# Sheet1.net
KiCad netlist of a schematic drawn in Altium Designer
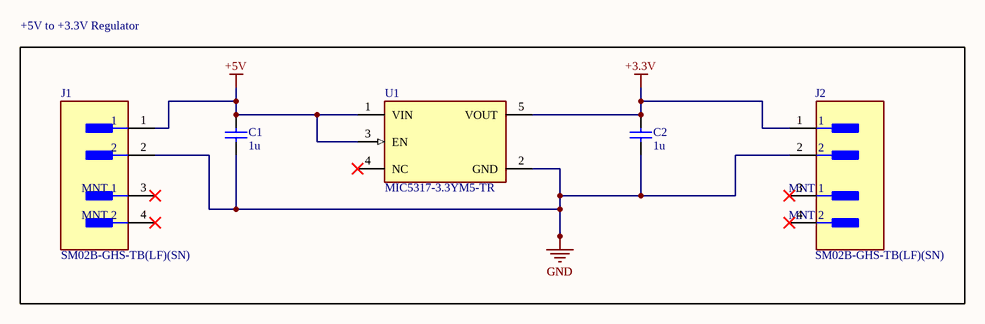
[diagram p0: Sheet1.SchDoc]

(export (version "E")
  (design (tool "Eeschema 10.0.6"))
  (components
    (comp (ref "C1")
      (value "1u")
      (footprint "CAPC2013X140X50ML20T25")
      (fields
        (field (name "MANUFACTURER") "AVX Interconnect / Elco")
        (field (name "PART NUMBER") "0805ZD105KAT2A")
      )
      (libsource (lib "Altium Content Vault") (part "CAP"))
    )
    (comp (ref "C2")
      (value "1u")
      (footprint "CAPC2013X140X50ML20T25")
      (fields
        (field (name "MANUFACTURER") "AVX Interconnect / Elco")
        (field (name "PART NUMBER") "0805ZD105KAT2A")
      )
      (libsource (lib "Altium Content Vault") (part "CAP"))
    )
    (comp (ref "J1")
      (value "SM02B-GHS-TB(LF)(SN)")
      (footprint "FP-SM02B-GHS-TB_LF_SN-MFG")
      (description "CONN HEADER SMD R/A 2POS 1.25MM")
      (libsource (lib "") (part "56ec3178a87b3978bdc1b3682cd516a_1"))
    )
    (comp (ref "J2")
      (value "SM02B-GHS-TB(LF)(SN)")
      (footprint "FP-SM02B-GHS-TB_LF_SN-MFG")
      (description "CONN HEADER SMD R/A 2POS 1.25MM")
      (libsource (lib "Altium Content Vault") (part "56ec3178a87b3978bdc1b3682cd516a"))
    )
    (comp (ref "U1")
      (value "MIC5317-3.3YM5-TR")
      (footprint "FP-SOT23-5LD-PL-1-MFG")
      (description "IC REG LINEAR 3.3V 150MA SOT23-5")
      (libsource (lib "Altium Content Vault") (part "0a093dae7315cdc977fd108dde87457"))
    )
  )
  (nets
    (net (code "1") (name "+3.3V") (class "Default")
      (node (ref "C2") (pin "2") (pinfunction "2_2") (pintype "passive"))
      (node (ref "J2") (pin "1") (pinfunction "1_1") (pintype "passive"))
      (node (ref "U1") (pin "5") (pinfunction "VOUT_5") (pintype "power_in"))
    )
    (net (code "2") (name "+5V") (class "Default")
      (node (ref "C1") (pin "1") (pinfunction "1_1") (pintype "passive"))
      (node (ref "J1") (pin "1") (pinfunction "1_1") (pintype "passive"))
      (node (ref "U1") (pin "1") (pinfunction "VIN_1") (pintype "power_in"))
      (node (ref "U1") (pin "3") (pinfunction "EN_3") (pintype "input"))
    )
    (net (code "3") (name "GND") (class "Default")
      (node (ref "C1") (pin "2") (pinfunction "2_2") (pintype "passive"))
      (node (ref "C2") (pin "1") (pinfunction "1_1") (pintype "passive"))
      (node (ref "J1") (pin "2") (pinfunction "2_2") (pintype "passive"))
      (node (ref "J2") (pin "2") (pinfunction "2_2") (pintype "passive"))
      (node (ref "U1") (pin "2") (pinfunction "GND_2") (pintype "power_in"))
    )
    (net (code "4") (name "unconnected-(J1-MNT_1-Pad3)") (class "Default")
      (node (ref "J1") (pin "3") (pinfunction "MNT_1_3") (pintype "passive+no_connect"))
    )
    (net (code "5") (name "unconnected-(J1-MNT_2-Pad4)") (class "Default")
      (node (ref "J1") (pin "4") (pinfunction "MNT_2_4") (pintype "passive+no_connect"))
    )
    (net (code "6") (name "unconnected-(J2-MNT_1-Pad3)") (class "Default")
      (node (ref "J2") (pin "3") (pinfunction "MNT_1_3") (pintype "passive+no_connect"))
    )
    (net (code "7") (name "unconnected-(J2-MNT_2-Pad4)") (class "Default")
      (node (ref "J2") (pin "4") (pinfunction "MNT_2_4") (pintype "passive+no_connect"))
    )
    (net (code "8") (name "unconnected-(U1-NC-Pad4)") (class "Default")
      (node (ref "U1") (pin "4") (pinfunction "NC_4") (pintype "passive+no_connect"))
    )
  )
)
